# MotorController.net
KiCad netlist of a schematic drawn in EAGLE
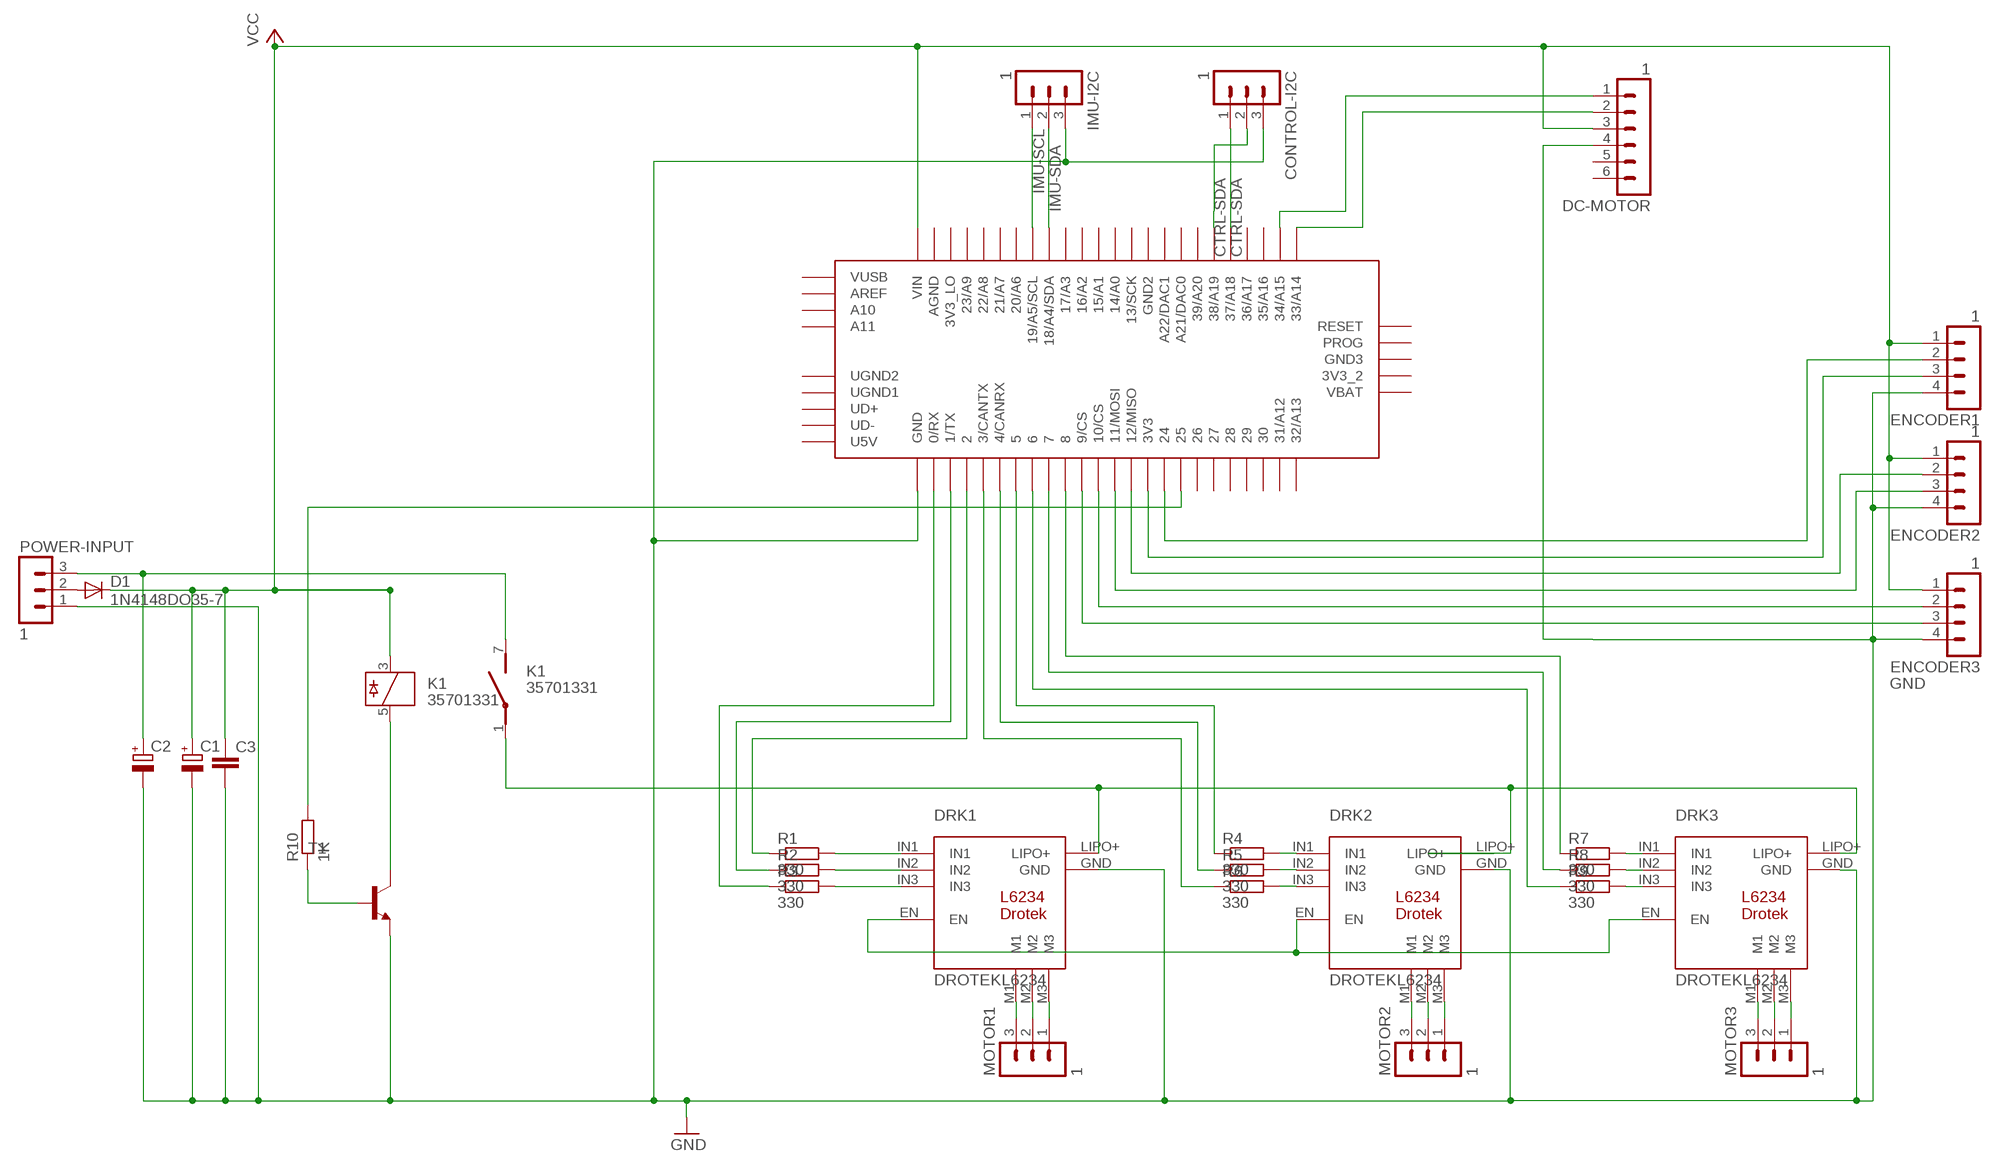
[diagram p0: schematic, sheet 1]

(export (version "E")
  (design (tool "Eeschema 10.0.6"))
  (components
    (comp (ref "C1")
      (value "CPOL-EUE7.5-16")
      (footprint "eagle-import:E7,5-16")
      (libsource (lib "eagle-import") (part "CPOL-EUE7.5-16"))
    )
    (comp (ref "C2")
      (value "CPOL-EUE7.5-16")
      (footprint "eagle-import:E7,5-16")
      (libsource (lib "eagle-import") (part "CPOL-EUE7.5-16"))
    )
    (comp (ref "C3")
      (value "C2.5/2")
      (footprint "eagle-import:C2.5-2")
      (libsource (lib "eagle-import") (part "C2.5/2"))
    )
    (comp (ref "CONTROL-I2C")
      (value "1")
      (footprint "eagle-import:MA03-1")
      (libsource (lib "eagle-import") (part "MA03-1"))
    )
    (comp (ref "D1")
      (value "1N4148DO35-7")
      (footprint "eagle-import:DO35-7")
      (libsource (lib "eagle-import") (part "1N4148DO35-7"))
    )
    (comp (ref "DC-MOTOR")
      (value "1")
      (footprint "eagle-import:MA06-1")
      (libsource (lib "eagle-import") (part "MA06-1"))
    )
    (comp (ref "DRK1")
      (value "DROTEKL6234")
      (footprint "eagle-import:DROTEKL6234")
      (libsource (lib "eagle-import") (part "DROTEKL6234"))
    )
    (comp (ref "DRK2")
      (value "DROTEKL6234")
      (footprint "eagle-import:DROTEKL6234")
      (libsource (lib "eagle-import") (part "DROTEKL6234"))
    )
    (comp (ref "DRK3")
      (value "DROTEKL6234")
      (footprint "eagle-import:DROTEKL6234")
      (libsource (lib "eagle-import") (part "DROTEKL6234"))
    )
    (comp (ref "ENCODER1")
      (value "1")
      (footprint "eagle-import:MA04-1")
      (libsource (lib "eagle-import") (part "MA04-1"))
    )
    (comp (ref "ENCODER2")
      (value "1")
      (footprint "eagle-import:MA04-1")
      (libsource (lib "eagle-import") (part "MA04-1"))
    )
    (comp (ref "ENCODER3")
      (value "1")
      (footprint "eagle-import:MA04-1")
      (libsource (lib "eagle-import") (part "MA04-1"))
    )
    (comp (ref "IMU-I2C")
      (value "1")
      (footprint "eagle-import:MA03-1")
      (libsource (lib "eagle-import") (part "MA03-1"))
    )
    (comp (ref "K1")
      (value "35701331")
      (footprint "eagle-import:REED")
      (libsource (lib "eagle-import") (part "35701331"))
    )
    (comp (ref "MOTOR1")
      (value "1")
      (footprint "eagle-import:MA03-1")
      (libsource (lib "eagle-import") (part "MA03-1"))
    )
    (comp (ref "MOTOR2")
      (value "1")
      (footprint "eagle-import:MA03-1")
      (libsource (lib "eagle-import") (part "MA03-1"))
    )
    (comp (ref "MOTOR3")
      (value "1")
      (footprint "eagle-import:MA03-1")
      (libsource (lib "eagle-import") (part "MA03-1"))
    )
    (comp (ref "POWER-INPUT")
      (value "1")
      (footprint "eagle-import:MA03-1")
      (libsource (lib "eagle-import") (part "MA03-1"))
    )
    (comp (ref "PRJ1")
      (value "TEENSY_3.5/3.6")
      (footprint "eagle-import:TEENSY_3.5_3.6")
      (libsource (lib "eagle-import") (part "TEENSY_3.5/3.6"))
    )
    (comp (ref "R1")
      (value "330")
      (footprint "eagle-import:0204_7")
      (libsource (lib "eagle-import") (part "R-EU_0204/7"))
    )
    (comp (ref "R2")
      (value "330")
      (footprint "eagle-import:0204_7")
      (libsource (lib "eagle-import") (part "R-EU_0204/7"))
    )
    (comp (ref "R3")
      (value "330")
      (footprint "eagle-import:0204_7")
      (libsource (lib "eagle-import") (part "R-EU_0204/7"))
    )
    (comp (ref "R4")
      (value "330")
      (footprint "eagle-import:0204_7")
      (libsource (lib "eagle-import") (part "R-EU_0204/7"))
    )
    (comp (ref "R5")
      (value "330")
      (footprint "eagle-import:0204_7")
      (libsource (lib "eagle-import") (part "R-EU_0204/7"))
    )
    (comp (ref "R6")
      (value "330")
      (footprint "eagle-import:0204_7")
      (libsource (lib "eagle-import") (part "R-EU_0204/7"))
    )
    (comp (ref "R7")
      (value "330")
      (footprint "eagle-import:0204_7")
      (libsource (lib "eagle-import") (part "R-EU_0204/7"))
    )
    (comp (ref "R8")
      (value "330")
      (footprint "eagle-import:0204_7")
      (libsource (lib "eagle-import") (part "R-EU_0204/7"))
    )
    (comp (ref "R9")
      (value "330")
      (footprint "eagle-import:0204_7")
      (libsource (lib "eagle-import") (part "R-EU_0204/7"))
    )
    (comp (ref "R10")
      (value "1K")
      (footprint "eagle-import:0204_7")
      (libsource (lib "eagle-import") (part "R-EU_0204/7"))
    )
    (comp (ref "T1")
      (value "-NPN-TO92")
      (footprint "eagle-import:TO92")
      (libsource (lib "eagle-import") (part "-NPN-TO92"))
    )
  )
  (nets
    (net (code "1") (name "/CTRL-SDA") (class "Default")
      (node (ref "CONTROL-I2C") (pin "1") (pinfunction "1_1") (pintype "passive"))
      (node (ref "PRJ1") (pin "37/A18") (pinfunction "37/A18_37/A18") (pintype "bidirectional"))
    )
    (net (code "2") (name "/IMU-SCL") (class "Default")
      (node (ref "IMU-I2C") (pin "1") (pinfunction "1_1") (pintype "passive"))
      (node (ref "PRJ1") (pin "19/A5/SCL") (pinfunction "19/A5/SCL_19/A5/SCL") (pintype "bidirectional"))
    )
    (net (code "3") (name "/IMU-SDA") (class "Default")
      (node (ref "IMU-I2C") (pin "2") (pinfunction "2_2") (pintype "passive"))
      (node (ref "PRJ1") (pin "18/A4/SDA") (pinfunction "18/A4/SDA_18/A4/SDA") (pintype "bidirectional"))
    )
    (net (code "4") (name "GND") (class "Default")
      (node (ref "C1") (pin "-") (pinfunction "-_-") (pintype "passive"))
      (node (ref "C2") (pin "-") (pinfunction "-_-") (pintype "passive"))
      (node (ref "C3") (pin "2") (pinfunction "2_2") (pintype "passive"))
      (node (ref "CONTROL-I2C") (pin "3") (pinfunction "3_3") (pintype "passive"))
      (node (ref "DC-MOTOR") (pin "4") (pinfunction "4_4") (pintype "passive"))
      (node (ref "DRK1") (pin "GND") (pinfunction "GND_GND") (pintype "input"))
      (node (ref "DRK2") (pin "GND") (pinfunction "GND_GND") (pintype "input"))
      (node (ref "DRK3") (pin "GND") (pinfunction "GND_GND") (pintype "input"))
      (node (ref "ENCODER1") (pin "4") (pinfunction "4_4") (pintype "passive"))
      (node (ref "ENCODER2") (pin "4") (pinfunction "4_4") (pintype "passive"))
      (node (ref "ENCODER3") (pin "4") (pinfunction "4_4") (pintype "passive"))
      (node (ref "IMU-I2C") (pin "3") (pinfunction "3_3") (pintype "passive"))
      (node (ref "POWER-INPUT") (pin "1") (pinfunction "1_1") (pintype "passive"))
      (node (ref "PRJ1") (pin "GND") (pinfunction "GND_GND") (pintype "bidirectional"))
      (node (ref "T1") (pin "1") (pinfunction "E_1") (pintype "passive"))
    )
    (net (code "5") (name "Net-(CONTROL-I2C-Pad2)") (class "Default")
      (node (ref "CONTROL-I2C") (pin "2") (pinfunction "2_2") (pintype "passive"))
      (node (ref "PRJ1") (pin "38/A19") (pinfunction "38/A19_38/A19") (pintype "bidirectional"))
    )
    (net (code "6") (name "Net-(D1-PadA)") (class "Default")
      (node (ref "D1") (pin "A") (pinfunction "A_A") (pintype "passive"))
      (node (ref "POWER-INPUT") (pin "2") (pinfunction "2_2") (pintype "passive"))
    )
    (net (code "7") (name "Net-(DC-MOTOR-Pad1)") (class "Default")
      (node (ref "DC-MOTOR") (pin "1") (pinfunction "1_1") (pintype "passive"))
      (node (ref "PRJ1") (pin "34/A15") (pinfunction "34/A15_34/A15") (pintype "bidirectional"))
    )
    (net (code "8") (name "Net-(DC-MOTOR-Pad2)") (class "Default")
      (node (ref "DC-MOTOR") (pin "2") (pinfunction "2_2") (pintype "passive"))
      (node (ref "PRJ1") (pin "33/A14") (pinfunction "33/A14_33/A14") (pintype "bidirectional"))
    )
    (net (code "9") (name "Net-(DRK1-PadEN)") (class "Default")
      (node (ref "DRK1") (pin "EN") (pinfunction "EN_EN") (pintype "bidirectional"))
      (node (ref "DRK2") (pin "EN") (pinfunction "EN_EN") (pintype "bidirectional"))
      (node (ref "DRK3") (pin "EN") (pinfunction "EN_EN") (pintype "bidirectional"))
    )
    (net (code "10") (name "Net-(DRK1-PadIN1)") (class "Default")
      (node (ref "DRK1") (pin "IN1") (pinfunction "IN1_IN1") (pintype "input"))
      (node (ref "R1") (pin "2") (pinfunction "2_2") (pintype "passive"))
    )
    (net (code "11") (name "Net-(DRK1-PadIN2)") (class "Default")
      (node (ref "DRK1") (pin "IN2") (pinfunction "IN2_IN2") (pintype "input"))
      (node (ref "R2") (pin "2") (pinfunction "2_2") (pintype "passive"))
    )
    (net (code "12") (name "Net-(DRK1-PadIN3)") (class "Default")
      (node (ref "DRK1") (pin "IN3") (pinfunction "IN3_IN3") (pintype "input"))
      (node (ref "R3") (pin "2") (pinfunction "2_2") (pintype "passive"))
    )
    (net (code "13") (name "Net-(DRK1-PadM1)") (class "Default")
      (node (ref "DRK1") (pin "M1") (pinfunction "M1_M1") (pintype "output"))
      (node (ref "MOTOR1") (pin "3") (pinfunction "3_3") (pintype "passive"))
    )
    (net (code "14") (name "Net-(DRK1-PadM2)") (class "Default")
      (node (ref "DRK1") (pin "M2") (pinfunction "M2_M2") (pintype "output"))
      (node (ref "MOTOR1") (pin "2") (pinfunction "2_2") (pintype "passive"))
    )
    (net (code "15") (name "Net-(DRK1-PadM3)") (class "Default")
      (node (ref "DRK1") (pin "M3") (pinfunction "M3_M3") (pintype "output"))
      (node (ref "MOTOR1") (pin "1") (pinfunction "1_1") (pintype "passive"))
    )
    (net (code "16") (name "Net-(DRK2-PadIN1)") (class "Default")
      (node (ref "DRK2") (pin "IN1") (pinfunction "IN1_IN1") (pintype "input"))
      (node (ref "R4") (pin "2") (pinfunction "2_2") (pintype "passive"))
    )
    (net (code "17") (name "Net-(DRK2-PadIN2)") (class "Default")
      (node (ref "DRK2") (pin "IN2") (pinfunction "IN2_IN2") (pintype "input"))
      (node (ref "R5") (pin "2") (pinfunction "2_2") (pintype "passive"))
    )
    (net (code "18") (name "Net-(DRK2-PadIN3)") (class "Default")
      (node (ref "DRK2") (pin "IN3") (pinfunction "IN3_IN3") (pintype "input"))
      (node (ref "R6") (pin "2") (pinfunction "2_2") (pintype "passive"))
    )
    (net (code "19") (name "Net-(DRK2-PadM1)") (class "Default")
      (node (ref "DRK2") (pin "M1") (pinfunction "M1_M1") (pintype "output"))
      (node (ref "MOTOR2") (pin "3") (pinfunction "3_3") (pintype "passive"))
    )
    (net (code "20") (name "Net-(DRK2-PadM2)") (class "Default")
      (node (ref "DRK2") (pin "M2") (pinfunction "M2_M2") (pintype "output"))
      (node (ref "MOTOR2") (pin "2") (pinfunction "2_2") (pintype "passive"))
    )
    (net (code "21") (name "Net-(DRK2-PadM3)") (class "Default")
      (node (ref "DRK2") (pin "M3") (pinfunction "M3_M3") (pintype "output"))
      (node (ref "MOTOR2") (pin "1") (pinfunction "1_1") (pintype "passive"))
    )
    (net (code "22") (name "Net-(DRK3-PadIN1)") (class "Default")
      (node (ref "DRK3") (pin "IN1") (pinfunction "IN1_IN1") (pintype "input"))
      (node (ref "R7") (pin "2") (pinfunction "2_2") (pintype "passive"))
    )
    (net (code "23") (name "Net-(DRK3-PadIN2)") (class "Default")
      (node (ref "DRK3") (pin "IN2") (pinfunction "IN2_IN2") (pintype "input"))
      (node (ref "R8") (pin "2") (pinfunction "2_2") (pintype "passive"))
    )
    (net (code "24") (name "Net-(DRK3-PadIN3)") (class "Default")
      (node (ref "DRK3") (pin "IN3") (pinfunction "IN3_IN3") (pintype "input"))
      (node (ref "R9") (pin "2") (pinfunction "2_2") (pintype "passive"))
    )
    (net (code "25") (name "Net-(DRK3-PadM1)") (class "Default")
      (node (ref "DRK3") (pin "M1") (pinfunction "M1_M1") (pintype "output"))
      (node (ref "MOTOR3") (pin "3") (pinfunction "3_3") (pintype "passive"))
    )
    (net (code "26") (name "Net-(DRK3-PadM2)") (class "Default")
      (node (ref "DRK3") (pin "M2") (pinfunction "M2_M2") (pintype "output"))
      (node (ref "MOTOR3") (pin "2") (pinfunction "2_2") (pintype "passive"))
    )
    (net (code "27") (name "Net-(DRK3-PadM3)") (class "Default")
      (node (ref "DRK3") (pin "M3") (pinfunction "M3_M3") (pintype "output"))
      (node (ref "MOTOR3") (pin "1") (pinfunction "1_1") (pintype "passive"))
    )
    (net (code "28") (name "Net-(ENCODER1-Pad2)") (class "Default")
      (node (ref "ENCODER1") (pin "2") (pinfunction "2_2") (pintype "passive"))
      (node (ref "PRJ1") (pin "24") (pinfunction "24_24") (pintype "bidirectional"))
    )
    (net (code "29") (name "Net-(ENCODER1-Pad3)") (class "Default")
      (node (ref "ENCODER1") (pin "3") (pinfunction "3_3") (pintype "passive"))
      (node (ref "PRJ1") (pin "3V3") (pinfunction "3V3_3V3") (pintype "bidirectional"))
    )
    (net (code "30") (name "Net-(ENCODER2-Pad2)") (class "Default")
      (node (ref "ENCODER2") (pin "2") (pinfunction "2_2") (pintype "passive"))
      (node (ref "PRJ1") (pin "12/MISO") (pinfunction "12/MISO_12/MISO") (pintype "bidirectional"))
    )
    (net (code "31") (name "Net-(ENCODER2-Pad3)") (class "Default")
      (node (ref "ENCODER2") (pin "3") (pinfunction "3_3") (pintype "passive"))
      (node (ref "PRJ1") (pin "11/MOSI") (pinfunction "11/MOSI_11/MOSI") (pintype "bidirectional"))
    )
    (net (code "32") (name "Net-(ENCODER3-Pad2)") (class "Default")
      (node (ref "ENCODER3") (pin "2") (pinfunction "2_2") (pintype "passive"))
      (node (ref "PRJ1") (pin "10/CS") (pinfunction "10/CS_10/CS") (pintype "bidirectional"))
    )
    (net (code "33") (name "Net-(ENCODER3-Pad3)") (class "Default")
      (node (ref "ENCODER3") (pin "3") (pinfunction "3_3") (pintype "passive"))
      (node (ref "PRJ1") (pin "9/CS") (pinfunction "9/CS_9/CS") (pintype "bidirectional"))
    )
    (net (code "34") (name "Net-(K1B-P)") (class "Default")
      (node (ref "DRK1") (pin "LIPO+") (pinfunction "LIPO+_LIPO+") (pintype "input"))
      (node (ref "DRK2") (pin "LIPO+") (pinfunction "LIPO+_LIPO+") (pintype "input"))
      (node (ref "DRK3") (pin "LIPO+") (pinfunction "LIPO+_LIPO+") (pintype "input"))
      (node (ref "K1") (pin "1") (pinfunction "P_1") (pintype "passive"))
    )
    (net (code "35") (name "Net-(K1B-S)") (class "Default")
      (node (ref "C2") (pin "+") (pinfunction "+_+") (pintype "passive"))
      (node (ref "K1") (pin "7") (pinfunction "S_7") (pintype "passive"))
      (node (ref "POWER-INPUT") (pin "3") (pinfunction "3_3") (pintype "passive"))
    )
    (net (code "36") (name "Net-(PRJ1-Pad0{slash}RX)") (class "Default")
      (node (ref "PRJ1") (pin "0/RX") (pinfunction "0/RX_0/RX") (pintype "bidirectional"))
      (node (ref "R3") (pin "1") (pinfunction "1_1") (pintype "passive"))
    )
    (net (code "37") (name "Net-(PRJ1-Pad1{slash}TX)") (class "Default")
      (node (ref "PRJ1") (pin "1/TX") (pinfunction "1/TX_1/TX") (pintype "bidirectional"))
      (node (ref "R2") (pin "1") (pinfunction "1_1") (pintype "passive"))
    )
    (net (code "38") (name "Net-(PRJ1-Pad2)") (class "Default")
      (node (ref "PRJ1") (pin "2") (pinfunction "2_2") (pintype "bidirectional"))
      (node (ref "R1") (pin "1") (pinfunction "1_1") (pintype "passive"))
    )
    (net (code "39") (name "Net-(PRJ1-Pad3{slash}CANTX)") (class "Default")
      (node (ref "PRJ1") (pin "3/CANTX") (pinfunction "3/CANTX_3/CANTX") (pintype "bidirectional"))
      (node (ref "R6") (pin "1") (pinfunction "1_1") (pintype "passive"))
    )
    (net (code "40") (name "Net-(PRJ1-Pad4{slash}CANRX)") (class "Default")
      (node (ref "PRJ1") (pin "4/CANRX") (pinfunction "4/CANRX_4/CANRX") (pintype "bidirectional"))
      (node (ref "R5") (pin "1") (pinfunction "1_1") (pintype "passive"))
    )
    (net (code "41") (name "Net-(PRJ1-Pad5)") (class "Default")
      (node (ref "PRJ1") (pin "5") (pinfunction "5_5") (pintype "bidirectional"))
      (node (ref "R4") (pin "1") (pinfunction "1_1") (pintype "passive"))
    )
    (net (code "42") (name "Net-(PRJ1-Pad6)") (class "Default")
      (node (ref "PRJ1") (pin "6") (pinfunction "6_6") (pintype "bidirectional"))
      (node (ref "R9") (pin "1") (pinfunction "1_1") (pintype "passive"))
    )
    (net (code "43") (name "Net-(PRJ1-Pad7)") (class "Default")
      (node (ref "PRJ1") (pin "7") (pinfunction "7_7") (pintype "bidirectional"))
      (node (ref "R8") (pin "1") (pinfunction "1_1") (pintype "passive"))
    )
    (net (code "44") (name "Net-(PRJ1-Pad8)") (class "Default")
      (node (ref "PRJ1") (pin "8") (pinfunction "8_8") (pintype "bidirectional"))
      (node (ref "R7") (pin "1") (pinfunction "1_1") (pintype "passive"))
    )
    (net (code "45") (name "Net-(PRJ1-Pad25)") (class "Default")
      (node (ref "PRJ1") (pin "25") (pinfunction "25_25") (pintype "bidirectional"))
      (node (ref "R10") (pin "2") (pinfunction "2_2") (pintype "passive"))
    )
    (net (code "46") (name "Net-(T1-B)") (class "Default")
      (node (ref "R10") (pin "1") (pinfunction "1_1") (pintype "passive"))
      (node (ref "T1") (pin "2") (pinfunction "B_2") (pintype "passive"))
    )
    (net (code "47") (name "Net-(T1-C)") (class "Default")
      (node (ref "K1") (pin "5") (pinfunction "5_5") (pintype "passive"))
      (node (ref "T1") (pin "3") (pinfunction "C_3") (pintype "passive"))
    )
    (net (code "48") (name "VCC") (class "Default")
      (node (ref "C1") (pin "+") (pinfunction "+_+") (pintype "passive"))
      (node (ref "C3") (pin "1") (pinfunction "1_1") (pintype "passive"))
      (node (ref "D1") (pin "C") (pinfunction "C_C") (pintype "passive"))
      (node (ref "DC-MOTOR") (pin "3") (pinfunction "3_3") (pintype "passive"))
      (node (ref "ENCODER1") (pin "1") (pinfunction "1_1") (pintype "passive"))
      (node (ref "ENCODER2") (pin "1") (pinfunction "1_1") (pintype "passive"))
      (node (ref "ENCODER3") (pin "1") (pinfunction "1_1") (pintype "passive"))
      (node (ref "K1") (pin "3") (pinfunction "3_3") (pintype "passive"))
      (node (ref "PRJ1") (pin "VIN") (pinfunction "VIN_VIN") (pintype "bidirectional"))
    )
    (net (code "49") (name "unconnected-(DC-MOTOR-Pad5)") (class "Default")
      (node (ref "DC-MOTOR") (pin "5") (pinfunction "5_5") (pintype "passive"))
    )
    (net (code "50") (name "unconnected-(DC-MOTOR-Pad6)") (class "Default")
      (node (ref "DC-MOTOR") (pin "6") (pinfunction "6_6") (pintype "passive"))
    )
    (net (code "51") (name "unconnected-(PRJ1-A21{slash}DAC0-Pad21{slash}DAC0)") (class "Default")
      (node (ref "PRJ1") (pin "21/DAC0") (pinfunction "A21/DAC0_21/DAC0") (pintype "bidirectional"))
    )
    (net (code "52") (name "unconnected-(PRJ1-Pad3V3_2)") (class "Default")
      (node (ref "PRJ1") (pin "3V3_2") (pinfunction "3V3_2_3V3_2") (pintype "bidirectional"))
    )
    (net (code "53") (name "unconnected-(PRJ1-Pad3V3_LO)") (class "Default")
      (node (ref "PRJ1") (pin "3V3_LO") (pinfunction "3V3_LO_3V3_LO") (pintype "bidirectional"))
    )
    (net (code "54") (name "unconnected-(PRJ1-Pad13{slash}SCK)") (class "Default")
      (node (ref "PRJ1") (pin "13/SCK") (pinfunction "13/SCK_13/SCK") (pintype "bidirectional"))
    )
    (net (code "55") (name "unconnected-(PRJ1-Pad14{slash}A0)") (class "Default")
      (node (ref "PRJ1") (pin "14/A0") (pinfunction "14/A0_14/A0") (pintype "bidirectional"))
    )
    (net (code "56") (name "unconnected-(PRJ1-Pad15{slash}A1)") (class "Default")
      (node (ref "PRJ1") (pin "15/A1") (pinfunction "15/A1_15/A1") (pintype "bidirectional"))
    )
    (net (code "57") (name "unconnected-(PRJ1-Pad16{slash}A2)") (class "Default")
      (node (ref "PRJ1") (pin "16/A2") (pinfunction "16/A2_16/A2") (pintype "bidirectional"))
    )
    (net (code "58") (name "unconnected-(PRJ1-Pad17{slash}A3)") (class "Default")
      (node (ref "PRJ1") (pin "17/A3") (pinfunction "17/A3_17/A3") (pintype "bidirectional"))
    )
    (net (code "59") (name "unconnected-(PRJ1-Pad20{slash}A6)") (class "Default")
      (node (ref "PRJ1") (pin "20/A6") (pinfunction "20/A6_20/A6") (pintype "bidirectional"))
    )
    (net (code "60") (name "unconnected-(PRJ1-Pad21{slash}A7)") (class "Default")
      (node (ref "PRJ1") (pin "21/A7") (pinfunction "21/A7_21/A7") (pintype "bidirectional"))
    )
    (net (code "61") (name "unconnected-(PRJ1-Pad22{slash}A8)") (class "Default")
      (node (ref "PRJ1") (pin "22/A8") (pinfunction "22/A8_22/A8") (pintype "bidirectional"))
    )
    (net (code "62") (name "unconnected-(PRJ1-Pad23{slash}A9)") (class "Default")
      (node (ref "PRJ1") (pin "23/A9") (pinfunction "23/A9_23/A9") (pintype "bidirectional"))
    )
    (net (code "63") (name "unconnected-(PRJ1-Pad26)") (class "Default")
      (node (ref "PRJ1") (pin "26") (pinfunction "26_26") (pintype "bidirectional"))
    )
    (net (code "64") (name "unconnected-(PRJ1-Pad27)") (class "Default")
      (node (ref "PRJ1") (pin "27") (pinfunction "27_27") (pintype "bidirectional"))
    )
    (net (code "65") (name "unconnected-(PRJ1-Pad28)") (class "Default")
      (node (ref "PRJ1") (pin "28") (pinfunction "28_28") (pintype "bidirectional"))
    )
    (net (code "66") (name "unconnected-(PRJ1-Pad29)") (class "Default")
      (node (ref "PRJ1") (pin "29") (pinfunction "29_29") (pintype "bidirectional"))
    )
    (net (code "67") (name "unconnected-(PRJ1-Pad30)") (class "Default")
      (node (ref "PRJ1") (pin "30") (pinfunction "30_30") (pintype "bidirectional"))
    )
    (net (code "68") (name "unconnected-(PRJ1-Pad31{slash}A12)") (class "Default")
      (node (ref "PRJ1") (pin "31/A12") (pinfunction "31/A12_31/A12") (pintype "bidirectional"))
    )
    (net (code "69") (name "unconnected-(PRJ1-Pad32{slash}A13)") (class "Default")
      (node (ref "PRJ1") (pin "32/A13") (pinfunction "32/A13_32/A13") (pintype "bidirectional"))
    )
    (net (code "70") (name "unconnected-(PRJ1-Pad35{slash}A16)") (class "Default")
      (node (ref "PRJ1") (pin "35/A16") (pinfunction "35/A16_35/A16") (pintype "bidirectional"))
    )
    (net (code "71") (name "unconnected-(PRJ1-Pad36{slash}A17)") (class "Default")
      (node (ref "PRJ1") (pin "36/A17") (pinfunction "36/A17_36/A17") (pintype "bidirectional"))
    )
    (net (code "72") (name "unconnected-(PRJ1-Pad39{slash}A20)") (class "Default")
      (node (ref "PRJ1") (pin "39/A20") (pinfunction "39/A20_39/A20") (pintype "bidirectional"))
    )
    (net (code "73") (name "unconnected-(PRJ1-PadA10)") (class "Default")
      (node (ref "PRJ1") (pin "A10") (pinfunction "A10_A10") (pintype "bidirectional"))
    )
    (net (code "74") (name "unconnected-(PRJ1-PadA11)") (class "Default")
      (node (ref "PRJ1") (pin "A11") (pinfunction "A11_A11") (pintype "bidirectional"))
    )
    (net (code "75") (name "unconnected-(PRJ1-PadA22{slash}DAC1)") (class "Default")
      (node (ref "PRJ1") (pin "A22/DAC1") (pinfunction "A22/DAC1_A22/DAC1") (pintype "bidirectional"))
    )
    (net (code "76") (name "unconnected-(PRJ1-PadAGND)") (class "Default")
      (node (ref "PRJ1") (pin "AGND") (pinfunction "AGND_AGND") (pintype "bidirectional"))
    )
    (net (code "77") (name "unconnected-(PRJ1-PadAREF)") (class "Default")
      (node (ref "PRJ1") (pin "AREF") (pinfunction "AREF_AREF") (pintype "bidirectional"))
    )
    (net (code "78") (name "unconnected-(PRJ1-PadGND2)") (class "Default")
      (node (ref "PRJ1") (pin "GND2") (pinfunction "GND2_GND2") (pintype "bidirectional"))
    )
    (net (code "79") (name "unconnected-(PRJ1-PadGND3)") (class "Default")
      (node (ref "PRJ1") (pin "GND3") (pinfunction "GND3_GND3") (pintype "bidirectional"))
    )
    (net (code "80") (name "unconnected-(PRJ1-PadPROG)") (class "Default")
      (node (ref "PRJ1") (pin "PROG") (pinfunction "PROG_PROG") (pintype "bidirectional"))
    )
    (net (code "81") (name "unconnected-(PRJ1-PadRESET)") (class "Default")
      (node (ref "PRJ1") (pin "RESET") (pinfunction "RESET_RESET") (pintype "bidirectional"))
    )
    (net (code "82") (name "unconnected-(PRJ1-PadU5V)") (class "Default")
      (node (ref "PRJ1") (pin "U5V") (pinfunction "U5V_U5V") (pintype "bidirectional"))
    )
    (net (code "83") (name "unconnected-(PRJ1-PadUD+)") (class "Default")
      (node (ref "PRJ1") (pin "UD+") (pinfunction "UD+_UD+") (pintype "bidirectional"))
    )
    (net (code "84") (name "unconnected-(PRJ1-PadUD-)") (class "Default")
      (node (ref "PRJ1") (pin "UD-") (pinfunction "UD-_UD-") (pintype "bidirectional"))
    )
    (net (code "85") (name "unconnected-(PRJ1-PadUGND1)") (class "Default")
      (node (ref "PRJ1") (pin "UGND1") (pinfunction "UGND1_UGND1") (pintype "bidirectional"))
    )
    (net (code "86") (name "unconnected-(PRJ1-PadUGND2)") (class "Default")
      (node (ref "PRJ1") (pin "UGND2") (pinfunction "UGND2_UGND2") (pintype "bidirectional"))
    )
    (net (code "87") (name "unconnected-(PRJ1-PadVBAT)") (class "Default")
      (node (ref "PRJ1") (pin "VBAT") (pinfunction "VBAT_VBAT") (pintype "bidirectional"))
    )
    (net (code "88") (name "unconnected-(PRJ1-PadVUSB)") (class "Default")
      (node (ref "PRJ1") (pin "VUSB") (pinfunction "VUSB_VUSB") (pintype "bidirectional"))
    )
  )
)
